# IMU.net
KiCad netlist of a schematic drawn in Altium Designer
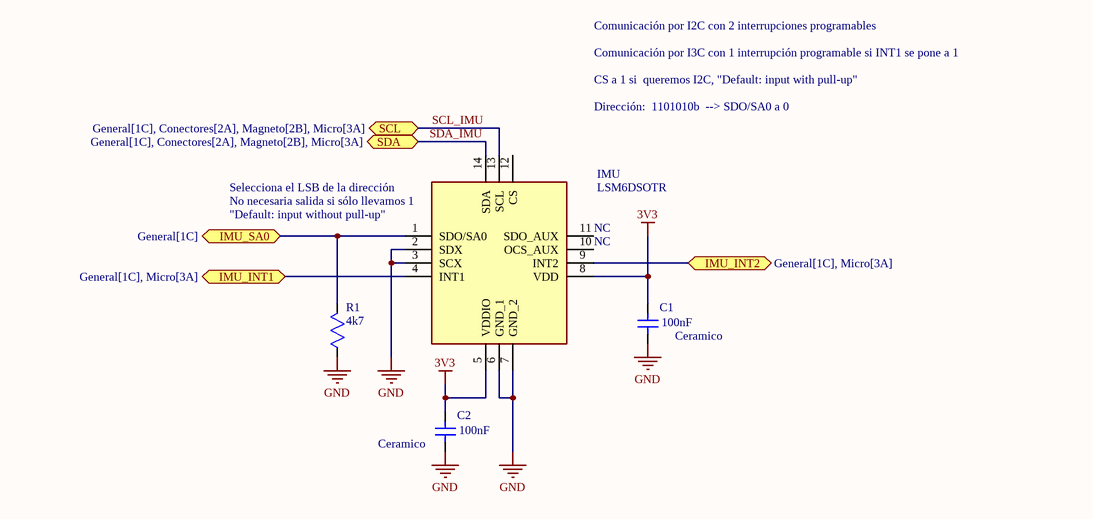
[diagram p0: IMU.SchDoc]

(export (version "E")
  (design (tool "Eeschema 10.0.6"))
  (components
    (comp (ref "C1")
      (value "CAP_0805_100nF")
      (footprint "CAP SMD 0805")
      (description "Condensador 0805 100nF")
      (fields (field (name "VALOR") "100nF"))
      (libsource (lib "ARUS Electronica") (part "CAP_0805_100nF"))
    )
    (comp (ref "C2")
      (value "CAP_0805_100nF")
      (footprint "CAP SMD 0805")
      (description "Condensador 0805 100nF")
      (fields (field (name "VALOR") "100nF"))
      (libsource (lib "ARUS Electronica") (part "CAP_0805_100nF"))
    )
    (comp (ref "IMU")
      (value "LSM6DSOTR")
      (footprint "SamacSys:LGA-14(2.5X3X0.86)")
      (description "Accelerometer")
      (fields (field (name "MOUSER PART NUMBER") "511-LSM6DSOTR"))
      (libsource (lib "*") (part "LSM6DSOTR"))
    )
    (comp (ref "R1")
      (value "RES_0805_4k7")
      (footprint "RES SMD 0805")
      (description "Resistencia 0805 4k7")
      (fields (field (name "VALOR") "4k7"))
      (libsource (lib "ARUS Electronica") (part "RES_2512_22R_2W"))
    )
  )
  (nets
    (net (code "1") (name "/IMU_INT1") (class "Default")
      (node (ref "IMU") (pin "4") (pinfunction "INT1_4") (pintype "passive"))
    )
    (net (code "2") (name "/IMU_INT2") (class "Default")
      (node (ref "IMU") (pin "9") (pinfunction "INT2_9") (pintype "passive"))
    )
    (net (code "3") (name "/IMU_SA0") (class "Default")
      (node (ref "IMU") (pin "1") (pinfunction "SDO/SA0_1") (pintype "passive"))
      (node (ref "R1") (pin "2") (pinfunction "2_2") (pintype "passive"))
    )
    (net (code "4") (name "/SCL_IMU") (class "Default")
      (node (ref "IMU") (pin "13") (pinfunction "SCL_13") (pintype "passive"))
    )
    (net (code "5") (name "/SDA_IMU") (class "Default")
      (node (ref "IMU") (pin "14") (pinfunction "SDA_14") (pintype "passive"))
    )
    (net (code "6") (name "3V3") (class "Default")
      (node (ref "C1") (pin "1") (pinfunction "1_1") (pintype "passive"))
      (node (ref "C2") (pin "1") (pinfunction "1_1") (pintype "passive"))
      (node (ref "IMU") (pin "5") (pinfunction "VDDIO_5") (pintype "passive"))
      (node (ref "IMU") (pin "8") (pinfunction "VDD_8") (pintype "passive"))
    )
    (net (code "7") (name "GND") (class "Default")
      (node (ref "C1") (pin "2") (pinfunction "2_2") (pintype "passive"))
      (node (ref "C2") (pin "2") (pinfunction "2_2") (pintype "passive"))
      (node (ref "IMU") (pin "2") (pinfunction "SDX_2") (pintype "passive"))
      (node (ref "IMU") (pin "3") (pinfunction "SCX_3") (pintype "passive"))
      (node (ref "IMU") (pin "6") (pinfunction "GND_1_6") (pintype "passive"))
      (node (ref "IMU") (pin "7") (pinfunction "GND_2_7") (pintype "passive"))
      (node (ref "R1") (pin "1") (pinfunction "1_1") (pintype "passive"))
    )
    (net (code "8") (name "unconnected-(IMU-CS-Pad12)") (class "Default")
      (node (ref "IMU") (pin "12") (pinfunction "CS_12") (pintype "passive"))
    )
    (net (code "9") (name "unconnected-(IMU-OCS_AUX-Pad10)") (class "Default")
      (node (ref "IMU") (pin "10") (pinfunction "OCS_AUX_10") (pintype "passive"))
    )
    (net (code "10") (name "unconnected-(IMU-SDO_AUX-Pad11)") (class "Default")
      (node (ref "IMU") (pin "11") (pinfunction "SDO_AUX_11") (pintype "passive"))
    )
  )
)
